# CD_Memory_New.net
KiCad netlist of a schematic drawn in EAGLE
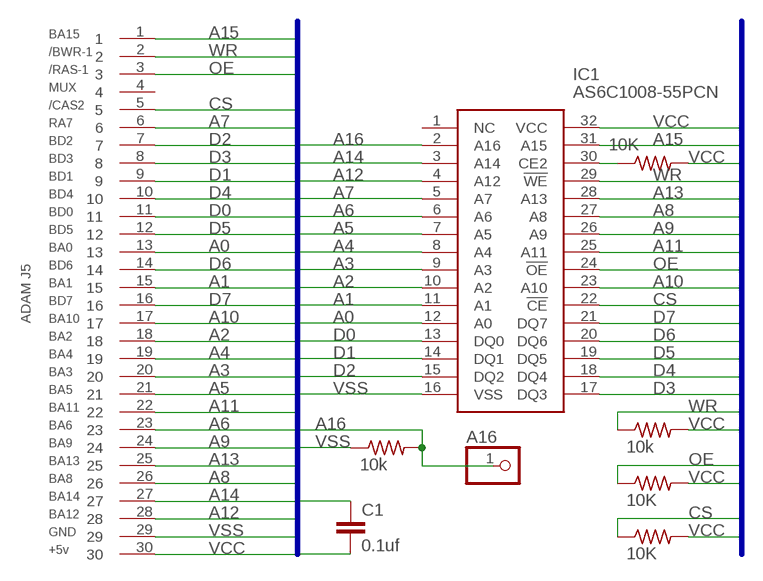
[diagram p0: schematic, sheet 1]

(export (version "E")
  (design (tool "Eeschema 10.0.6"))
  (components
    (comp (ref "A16")
      (value "PINHD-1X1")
      (footprint "eagle-import:1X01")
      (libsource (lib "eagle-import") (part "PINHD-1X1"))
    )
    (comp (ref "C1")
      (value "0.1uf")
      (footprint "eagle-import:C050-030X075")
      (libsource (lib "eagle-import") (part "C-EU050-030X075"))
    )
    (comp (ref "IC1")
      (value "AS6C1008-55PCN")
      (footprint "eagle-import:DIP254P1524X393-32")
      (fields (field (name "MOUSER_PART_NUMBER") "913-AS6C1008-55PCN"))
      (libsource (lib "eagle-import") (part "AS6C1008-55PCN"))
    )
    (comp (ref "R1")
      (value "10K")
      (footprint "eagle-import:V526-0")
      (libsource (lib "eagle-import") (part "R-US_V526-0"))
    )
    (comp (ref "R2")
      (value "10k")
      (footprint "eagle-import:V526-0")
      (libsource (lib "eagle-import") (part "R-US_V526-0"))
    )
    (comp (ref "R3")
      (value "10K")
      (footprint "eagle-import:V526-0")
      (libsource (lib "eagle-import") (part "R-US_V526-0"))
    )
    (comp (ref "R4")
      (value "10K")
      (footprint "eagle-import:V526-0")
      (libsource (lib "eagle-import") (part "R-US_V526-0"))
    )
    (comp (ref "R5")
      (value "10k")
      (footprint "eagle-import:V526-0")
      (libsource (lib "eagle-import") (part "R-US_V526-0"))
    )
    (comp (ref "U$1")
      (value "MEM_CARD_NO_OUTLINE")
      (footprint "eagle-import:J5CARD_NO_OUTLINE")
      (libsource (lib "eagle-import") (part "MEM_CARD_NO_OUTLINE"))
    )
  )
  (nets
    (net (code "1") (name "/A0") (class "Default")
      (node (ref "IC1") (pin "12") (pinfunction "A0_12") (pintype "bidirectional"))
      (node (ref "U$1") (pin "13") (pinfunction "13_13") (pintype "bidirectional"))
    )
    (net (code "2") (name "/A1") (class "Default")
      (node (ref "IC1") (pin "11") (pinfunction "A1_11") (pintype "bidirectional"))
      (node (ref "U$1") (pin "15") (pinfunction "15_15") (pintype "bidirectional"))
    )
    (net (code "3") (name "/A2") (class "Default")
      (node (ref "IC1") (pin "10") (pinfunction "A2_10") (pintype "bidirectional"))
      (node (ref "U$1") (pin "18") (pinfunction "18_18") (pintype "bidirectional"))
    )
    (net (code "4") (name "/A3") (class "Default")
      (node (ref "IC1") (pin "9") (pinfunction "A3_9") (pintype "bidirectional"))
      (node (ref "U$1") (pin "20") (pinfunction "20_20") (pintype "bidirectional"))
    )
    (net (code "5") (name "/A4") (class "Default")
      (node (ref "IC1") (pin "8") (pinfunction "A4_8") (pintype "bidirectional"))
      (node (ref "U$1") (pin "19") (pinfunction "19_19") (pintype "bidirectional"))
    )
    (net (code "6") (name "/A5") (class "Default")
      (node (ref "IC1") (pin "7") (pinfunction "A5_7") (pintype "bidirectional"))
      (node (ref "U$1") (pin "21") (pinfunction "21_21") (pintype "bidirectional"))
    )
    (net (code "7") (name "/A6") (class "Default")
      (node (ref "IC1") (pin "6") (pinfunction "A6_6") (pintype "bidirectional"))
      (node (ref "U$1") (pin "23") (pinfunction "23_23") (pintype "bidirectional"))
    )
    (net (code "8") (name "/A7") (class "Default")
      (node (ref "IC1") (pin "5") (pinfunction "A7_5") (pintype "bidirectional"))
      (node (ref "U$1") (pin "6") (pinfunction "6_6") (pintype "bidirectional"))
    )
    (net (code "9") (name "/A8") (class "Default")
      (node (ref "IC1") (pin "27") (pinfunction "A8_27") (pintype "bidirectional"))
      (node (ref "U$1") (pin "26") (pinfunction "26_26") (pintype "bidirectional"))
    )
    (net (code "10") (name "/A9") (class "Default")
      (node (ref "IC1") (pin "26") (pinfunction "A9_26") (pintype "bidirectional"))
      (node (ref "U$1") (pin "24") (pinfunction "24_24") (pintype "bidirectional"))
    )
    (net (code "11") (name "/A10") (class "Default")
      (node (ref "IC1") (pin "23") (pinfunction "A10_23") (pintype "bidirectional"))
      (node (ref "U$1") (pin "17") (pinfunction "17_17") (pintype "bidirectional"))
    )
    (net (code "12") (name "/A11") (class "Default")
      (node (ref "IC1") (pin "25") (pinfunction "A11_25") (pintype "bidirectional"))
      (node (ref "U$1") (pin "22") (pinfunction "22_22") (pintype "bidirectional"))
    )
    (net (code "13") (name "/A12") (class "Default")
      (node (ref "IC1") (pin "4") (pinfunction "A12_4") (pintype "bidirectional"))
      (node (ref "U$1") (pin "28") (pinfunction "28_28") (pintype "bidirectional"))
    )
    (net (code "14") (name "/A13") (class "Default")
      (node (ref "IC1") (pin "28") (pinfunction "A13_28") (pintype "bidirectional"))
      (node (ref "U$1") (pin "25") (pinfunction "25_25") (pintype "bidirectional"))
    )
    (net (code "15") (name "/A14") (class "Default")
      (node (ref "IC1") (pin "3") (pinfunction "A14_3") (pintype "bidirectional"))
      (node (ref "U$1") (pin "27") (pinfunction "27_27") (pintype "bidirectional"))
    )
    (net (code "16") (name "/A15") (class "Default")
      (node (ref "IC1") (pin "31") (pinfunction "A15_31") (pintype "bidirectional"))
      (node (ref "U$1") (pin "1") (pinfunction "1_1") (pintype "bidirectional"))
    )
    (net (code "17") (name "/A16") (class "Default")
      (node (ref "A16") (pin "1") (pinfunction "1_1") (pintype "passive"))
      (node (ref "IC1") (pin "2") (pinfunction "A16_2") (pintype "bidirectional"))
      (node (ref "R5") (pin "2") (pinfunction "2_2") (pintype "passive"))
    )
    (net (code "18") (name "/CS") (class "Default")
      (node (ref "IC1") (pin "22") (pinfunction "~{CE}_22") (pintype "bidirectional"))
      (node (ref "R4") (pin "1") (pinfunction "1_1") (pintype "passive"))
      (node (ref "U$1") (pin "5") (pinfunction "5_5") (pintype "bidirectional"))
    )
    (net (code "19") (name "/D0") (class "Default")
      (node (ref "IC1") (pin "13") (pinfunction "DQ0_13") (pintype "bidirectional"))
      (node (ref "U$1") (pin "11") (pinfunction "11_11") (pintype "bidirectional"))
    )
    (net (code "20") (name "/D1") (class "Default")
      (node (ref "IC1") (pin "14") (pinfunction "DQ1_14") (pintype "bidirectional"))
      (node (ref "U$1") (pin "9") (pinfunction "9_9") (pintype "bidirectional"))
    )
    (net (code "21") (name "/D2") (class "Default")
      (node (ref "IC1") (pin "15") (pinfunction "DQ2_15") (pintype "bidirectional"))
      (node (ref "U$1") (pin "7") (pinfunction "7_7") (pintype "bidirectional"))
    )
    (net (code "22") (name "/D3") (class "Default")
      (node (ref "IC1") (pin "17") (pinfunction "DQ3_17") (pintype "bidirectional"))
      (node (ref "U$1") (pin "8") (pinfunction "8_8") (pintype "bidirectional"))
    )
    (net (code "23") (name "/D4") (class "Default")
      (node (ref "IC1") (pin "18") (pinfunction "DQ4_18") (pintype "bidirectional"))
      (node (ref "U$1") (pin "10") (pinfunction "10_10") (pintype "bidirectional"))
    )
    (net (code "24") (name "/D5") (class "Default")
      (node (ref "IC1") (pin "19") (pinfunction "DQ5_19") (pintype "bidirectional"))
      (node (ref "U$1") (pin "12") (pinfunction "12_12") (pintype "bidirectional"))
    )
    (net (code "25") (name "/D6") (class "Default")
      (node (ref "IC1") (pin "20") (pinfunction "DQ6_20") (pintype "bidirectional"))
      (node (ref "U$1") (pin "14") (pinfunction "14_14") (pintype "bidirectional"))
    )
    (net (code "26") (name "/D7") (class "Default")
      (node (ref "IC1") (pin "21") (pinfunction "DQ7_21") (pintype "bidirectional"))
      (node (ref "U$1") (pin "16") (pinfunction "16_16") (pintype "bidirectional"))
    )
    (net (code "27") (name "/OE") (class "Default")
      (node (ref "IC1") (pin "24") (pinfunction "~{OE}_24") (pintype "bidirectional"))
      (node (ref "R3") (pin "1") (pinfunction "1_1") (pintype "passive"))
      (node (ref "U$1") (pin "3") (pinfunction "3_3") (pintype "bidirectional"))
    )
    (net (code "28") (name "/VCC") (class "Default")
      (node (ref "C1") (pin "2") (pinfunction "2_2") (pintype "passive"))
      (node (ref "IC1") (pin "32") (pinfunction "VCC_32") (pintype "bidirectional"))
      (node (ref "R1") (pin "2") (pinfunction "2_2") (pintype "passive"))
      (node (ref "R2") (pin "2") (pinfunction "2_2") (pintype "passive"))
      (node (ref "R3") (pin "2") (pinfunction "2_2") (pintype "passive"))
      (node (ref "R4") (pin "2") (pinfunction "2_2") (pintype "passive"))
      (node (ref "U$1") (pin "30") (pinfunction "30_30") (pintype "bidirectional"))
    )
    (net (code "29") (name "/VSS") (class "Default")
      (node (ref "C1") (pin "1") (pinfunction "1_1") (pintype "passive"))
      (node (ref "IC1") (pin "16") (pinfunction "VSS_16") (pintype "bidirectional"))
      (node (ref "R5") (pin "1") (pinfunction "1_1") (pintype "passive"))
      (node (ref "U$1") (pin "29") (pinfunction "29_29") (pintype "bidirectional"))
    )
    (net (code "30") (name "/WR") (class "Default")
      (node (ref "IC1") (pin "29") (pinfunction "~{WE}_29") (pintype "bidirectional"))
      (node (ref "R2") (pin "1") (pinfunction "1_1") (pintype "passive"))
      (node (ref "U$1") (pin "2") (pinfunction "2_2") (pintype "bidirectional"))
    )
    (net (code "32") (name "Net-(IC1-CE2)") (class "Default")
      (node (ref "IC1") (pin "30") (pinfunction "CE2_30") (pintype "bidirectional"))
      (node (ref "R1") (pin "1") (pinfunction "1_1") (pintype "passive"))
    )
    (net (code "33") (name "unconnected-(IC1-NC-Pad1)") (class "Default")
      (node (ref "IC1") (pin "1") (pinfunction "NC_1") (pintype "no_connect"))
    )
    (net (code "34") (name "unconnected-(U$1-Pad4)") (class "Default")
      (node (ref "U$1") (pin "4") (pinfunction "4_4") (pintype "bidirectional"))
    )
  )
)
